# LiFePO4wered-USB-3.net
KiCad netlist of a schematic drawn in EAGLE
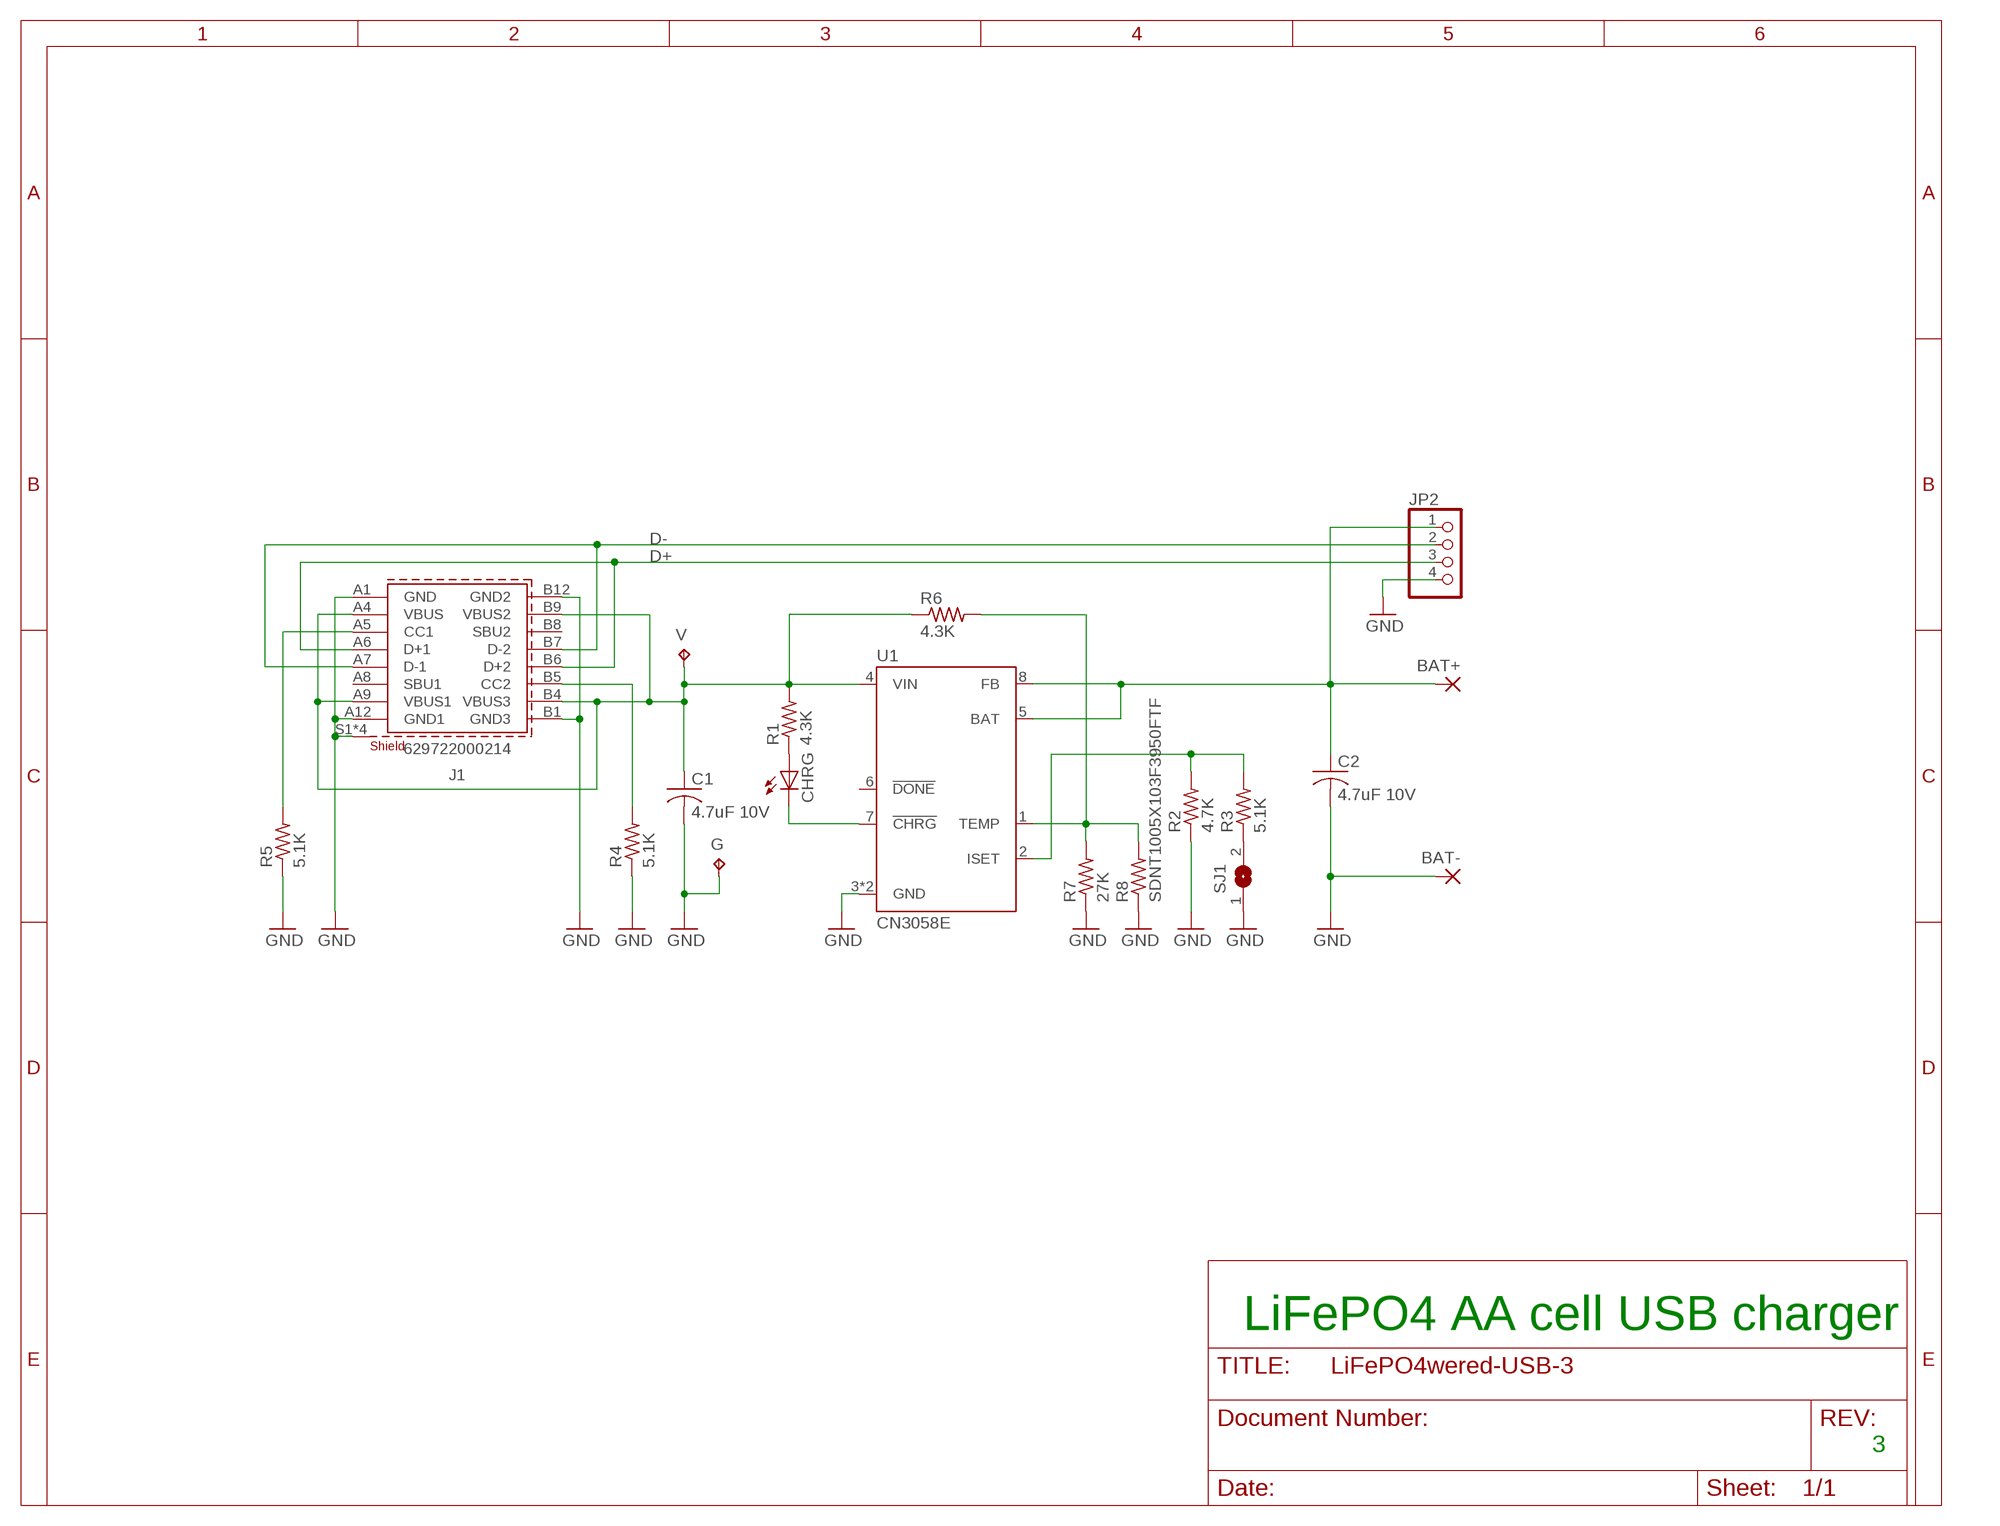
[diagram p0: schematic, sheet 1]

(export (version "E")
  (design (tool "Eeschema 10.0.6"))
  (components
    (comp (ref "BAT+")
      (value "2,54/1,0")
      (footprint "eagle-import:2,54_1,0")
      (libsource (lib "eagle-import") (part "2,54/1,0"))
    )
    (comp (ref "BAT-")
      (value "2,54/1,0")
      (footprint "eagle-import:2,54_1,0")
      (libsource (lib "eagle-import") (part "2,54/1,0"))
    )
    (comp (ref "C1")
      (value "4.7uF 10V")
      (footprint "eagle-import:C0603")
      (libsource (lib "eagle-import") (part "C-USC0603"))
    )
    (comp (ref "C2")
      (value "4.7uF 10V")
      (footprint "eagle-import:C0603")
      (libsource (lib "eagle-import") (part "C-USC0603"))
    )
    (comp (ref "CHRG")
      (value "LEDCHIP-LED0603")
      (footprint "eagle-import:CHIP-LED0603")
      (libsource (lib "eagle-import") (part "LEDCHIP-LED0603"))
    )
    (comp (ref "G")
      (value "TPTP20R")
      (footprint "eagle-import:TP20R")
      (libsource (lib "eagle-import") (part "TPTP20R"))
    )
    (comp (ref "J1")
      (value "629722000214")
      (footprint "eagle-import:629722000214")
      (libsource (lib "eagle-import") (part "629722000214"))
    )
    (comp (ref "JP2")
      (value "PINHD-1X4")
      (footprint "eagle-import:1X04")
      (libsource (lib "eagle-import") (part "PINHD-1X4"))
    )
    (comp (ref "R1")
      (value "4.3K")
      (footprint "eagle-import:R0402")
      (libsource (lib "eagle-import") (part "R-US_R0402"))
    )
    (comp (ref "R2")
      (value "4.7K")
      (footprint "eagle-import:R0402")
      (libsource (lib "eagle-import") (part "R-US_R0402"))
    )
    (comp (ref "R3")
      (value "5.1K")
      (footprint "eagle-import:R0402")
      (libsource (lib "eagle-import") (part "R-US_R0402"))
    )
    (comp (ref "R4")
      (value "5.1K")
      (footprint "eagle-import:R0402")
      (libsource (lib "eagle-import") (part "R-US_R0402"))
    )
    (comp (ref "R5")
      (value "5.1K")
      (footprint "eagle-import:R0402")
      (libsource (lib "eagle-import") (part "R-US_R0402"))
    )
    (comp (ref "R6")
      (value "4.3K")
      (footprint "eagle-import:R0402")
      (libsource (lib "eagle-import") (part "R-US_R0402"))
    )
    (comp (ref "R7")
      (value "27K")
      (footprint "eagle-import:R0402")
      (libsource (lib "eagle-import") (part "R-US_R0402"))
    )
    (comp (ref "R8")
      (value "SDNT1005X103F3950FTF")
      (footprint "eagle-import:R0402")
      (libsource (lib "eagle-import") (part "R-US_R0402"))
    )
    (comp (ref "SJ1") (value "SJ") (footprint "eagle-import:SJ") (libsource (lib "eagle-import") (part "SJ")))
    (comp (ref "U1")
      (value "CN3058E")
      (footprint "eagle-import:SO08-THERMAL")
      (libsource (lib "eagle-import") (part "CN3058E"))
    )
    (comp (ref "V")
      (value "TPTP20R")
      (footprint "eagle-import:TP20R")
      (libsource (lib "eagle-import") (part "TPTP20R"))
    )
  )
  (nets
    (net (code "1") (name "/D+") (class "Default")
      (node (ref "J1") (pin "A6") (pinfunction "D+1_A6") (pintype "passive"))
      (node (ref "J1") (pin "B6") (pinfunction "D+2_B6") (pintype "passive"))
      (node (ref "JP2") (pin "3") (pinfunction "3_3") (pintype "passive"))
    )
    (net (code "2") (name "/D-") (class "Default")
      (node (ref "J1") (pin "A7") (pinfunction "D-1_A7") (pintype "passive"))
      (node (ref "J1") (pin "B7") (pinfunction "D-2_B7") (pintype "passive"))
      (node (ref "JP2") (pin "2") (pinfunction "2_2") (pintype "passive"))
    )
    (net (code "3") (name "GND") (class "Default")
      (node (ref "BAT-") (pin "1") (pinfunction "P_1") (pintype "passive"))
      (node (ref "C1") (pin "2") (pinfunction "2_2") (pintype "passive"))
      (node (ref "C2") (pin "2") (pinfunction "2_2") (pintype "passive"))
      (node (ref "G") (pin "TP") (pinfunction "TP_TP") (pintype "input"))
      (node (ref "J1") (pin "A1") (pinfunction "GND_A1") (pintype "passive"))
      (node (ref "J1") (pin "A12") (pinfunction "GND1_A12") (pintype "passive"))
      (node (ref "J1") (pin "B1") (pinfunction "GND3_B1") (pintype "passive"))
      (node (ref "J1") (pin "B12") (pinfunction "GND2_B12") (pintype "passive"))
      (node (ref "J1") (pin "S1") (pinfunction "SHIELD_S1") (pintype "passive"))
      (node (ref "J1") (pin "S2") (pinfunction "SHIELD_S2") (pintype "passive"))
      (node (ref "J1") (pin "S3") (pinfunction "SHIELD_S3") (pintype "passive"))
      (node (ref "J1") (pin "S4") (pinfunction "SHIELD_S4") (pintype "passive"))
      (node (ref "JP2") (pin "4") (pinfunction "4_4") (pintype "passive"))
      (node (ref "R2") (pin "1") (pinfunction "1_1") (pintype "passive"))
      (node (ref "R4") (pin "1") (pinfunction "1_1") (pintype "passive"))
      (node (ref "R5") (pin "1") (pinfunction "1_1") (pintype "passive"))
      (node (ref "R7") (pin "1") (pinfunction "1_1") (pintype "passive"))
      (node (ref "R8") (pin "1") (pinfunction "1_1") (pintype "passive"))
      (node (ref "SJ1") (pin "1") (pinfunction "1_1") (pintype "passive"))
      (node (ref "U1") (pin "3") (pinfunction "GND_3") (pintype "bidirectional"))
      (node (ref "U1") (pin "PAD") (pinfunction "GND_PAD") (pintype "bidirectional"))
    )
    (net (code "4") (name "Net-(BAT+-P)") (class "Default")
      (node (ref "BAT+") (pin "1") (pinfunction "P_1") (pintype "passive"))
      (node (ref "C2") (pin "1") (pinfunction "1_1") (pintype "passive"))
      (node (ref "JP2") (pin "1") (pinfunction "1_1") (pintype "passive"))
      (node (ref "U1") (pin "5") (pinfunction "BAT_5") (pintype "bidirectional"))
      (node (ref "U1") (pin "8") (pinfunction "FB_8") (pintype "bidirectional"))
    )
    (net (code "5") (name "Net-(CHRG-PadA)") (class "Default")
      (node (ref "CHRG") (pin "A") (pinfunction "A_A") (pintype "passive"))
      (node (ref "R1") (pin "1") (pinfunction "1_1") (pintype "passive"))
    )
    (net (code "6") (name "Net-(J1-CC1)") (class "Default")
      (node (ref "J1") (pin "A5") (pinfunction "CC1_A5") (pintype "passive"))
      (node (ref "R5") (pin "2") (pinfunction "2_2") (pintype "passive"))
    )
    (net (code "7") (name "Net-(J1-CC2)") (class "Default")
      (node (ref "J1") (pin "B5") (pinfunction "CC2_B5") (pintype "passive"))
      (node (ref "R4") (pin "2") (pinfunction "2_2") (pintype "passive"))
    )
    (net (code "8") (name "Net-(J1-VBUS)") (class "Default")
      (node (ref "C1") (pin "1") (pinfunction "1_1") (pintype "passive"))
      (node (ref "J1") (pin "A4") (pinfunction "VBUS_A4") (pintype "passive"))
      (node (ref "J1") (pin "A9") (pinfunction "VBUS1_A9") (pintype "passive"))
      (node (ref "J1") (pin "B4") (pinfunction "VBUS3_B4") (pintype "passive"))
      (node (ref "J1") (pin "B9") (pinfunction "VBUS2_B9") (pintype "passive"))
      (node (ref "R1") (pin "2") (pinfunction "2_2") (pintype "passive"))
      (node (ref "R6") (pin "1") (pinfunction "1_1") (pintype "passive"))
      (node (ref "U1") (pin "4") (pinfunction "VIN_4") (pintype "bidirectional"))
      (node (ref "V") (pin "TP") (pinfunction "TP_TP") (pintype "input"))
    )
    (net (code "9") (name "Net-(R3-Pad1)") (class "Default")
      (node (ref "R3") (pin "1") (pinfunction "1_1") (pintype "passive"))
      (node (ref "SJ1") (pin "2") (pinfunction "2_2") (pintype "passive"))
    )
    (net (code "10") (name "Net-(U1-ISET)") (class "Default")
      (node (ref "R2") (pin "2") (pinfunction "2_2") (pintype "passive"))
      (node (ref "R3") (pin "2") (pinfunction "2_2") (pintype "passive"))
      (node (ref "U1") (pin "2") (pinfunction "ISET_2") (pintype "bidirectional"))
    )
    (net (code "11") (name "Net-(U1-TEMP)") (class "Default")
      (node (ref "R6") (pin "2") (pinfunction "2_2") (pintype "passive"))
      (node (ref "R7") (pin "2") (pinfunction "2_2") (pintype "passive"))
      (node (ref "R8") (pin "2") (pinfunction "2_2") (pintype "passive"))
      (node (ref "U1") (pin "1") (pinfunction "TEMP_1") (pintype "bidirectional"))
    )
    (net (code "12") (name "Net-(U1-~{CHRG})") (class "Default")
      (node (ref "CHRG") (pin "C") (pinfunction "C_C") (pintype "passive"))
      (node (ref "U1") (pin "7") (pinfunction "~{CHRG}_7") (pintype "bidirectional"))
    )
    (net (code "13") (name "unconnected-(J1-SBU1-PadA8)") (class "Default")
      (node (ref "J1") (pin "A8") (pinfunction "SBU1_A8") (pintype "passive"))
    )
    (net (code "14") (name "unconnected-(J1-SBU2-PadB8)") (class "Default")
      (node (ref "J1") (pin "B8") (pinfunction "SBU2_B8") (pintype "passive"))
    )
    (net (code "15") (name "unconnected-(U1-~{DONE}-Pad6)") (class "Default")
      (node (ref "U1") (pin "6") (pinfunction "~{DONE}_6") (pintype "bidirectional"))
    )
  )
)
